# 23_-_SENSORS_CAN_IR.net
KiCad netlist of a schematic drawn in Altium Designer
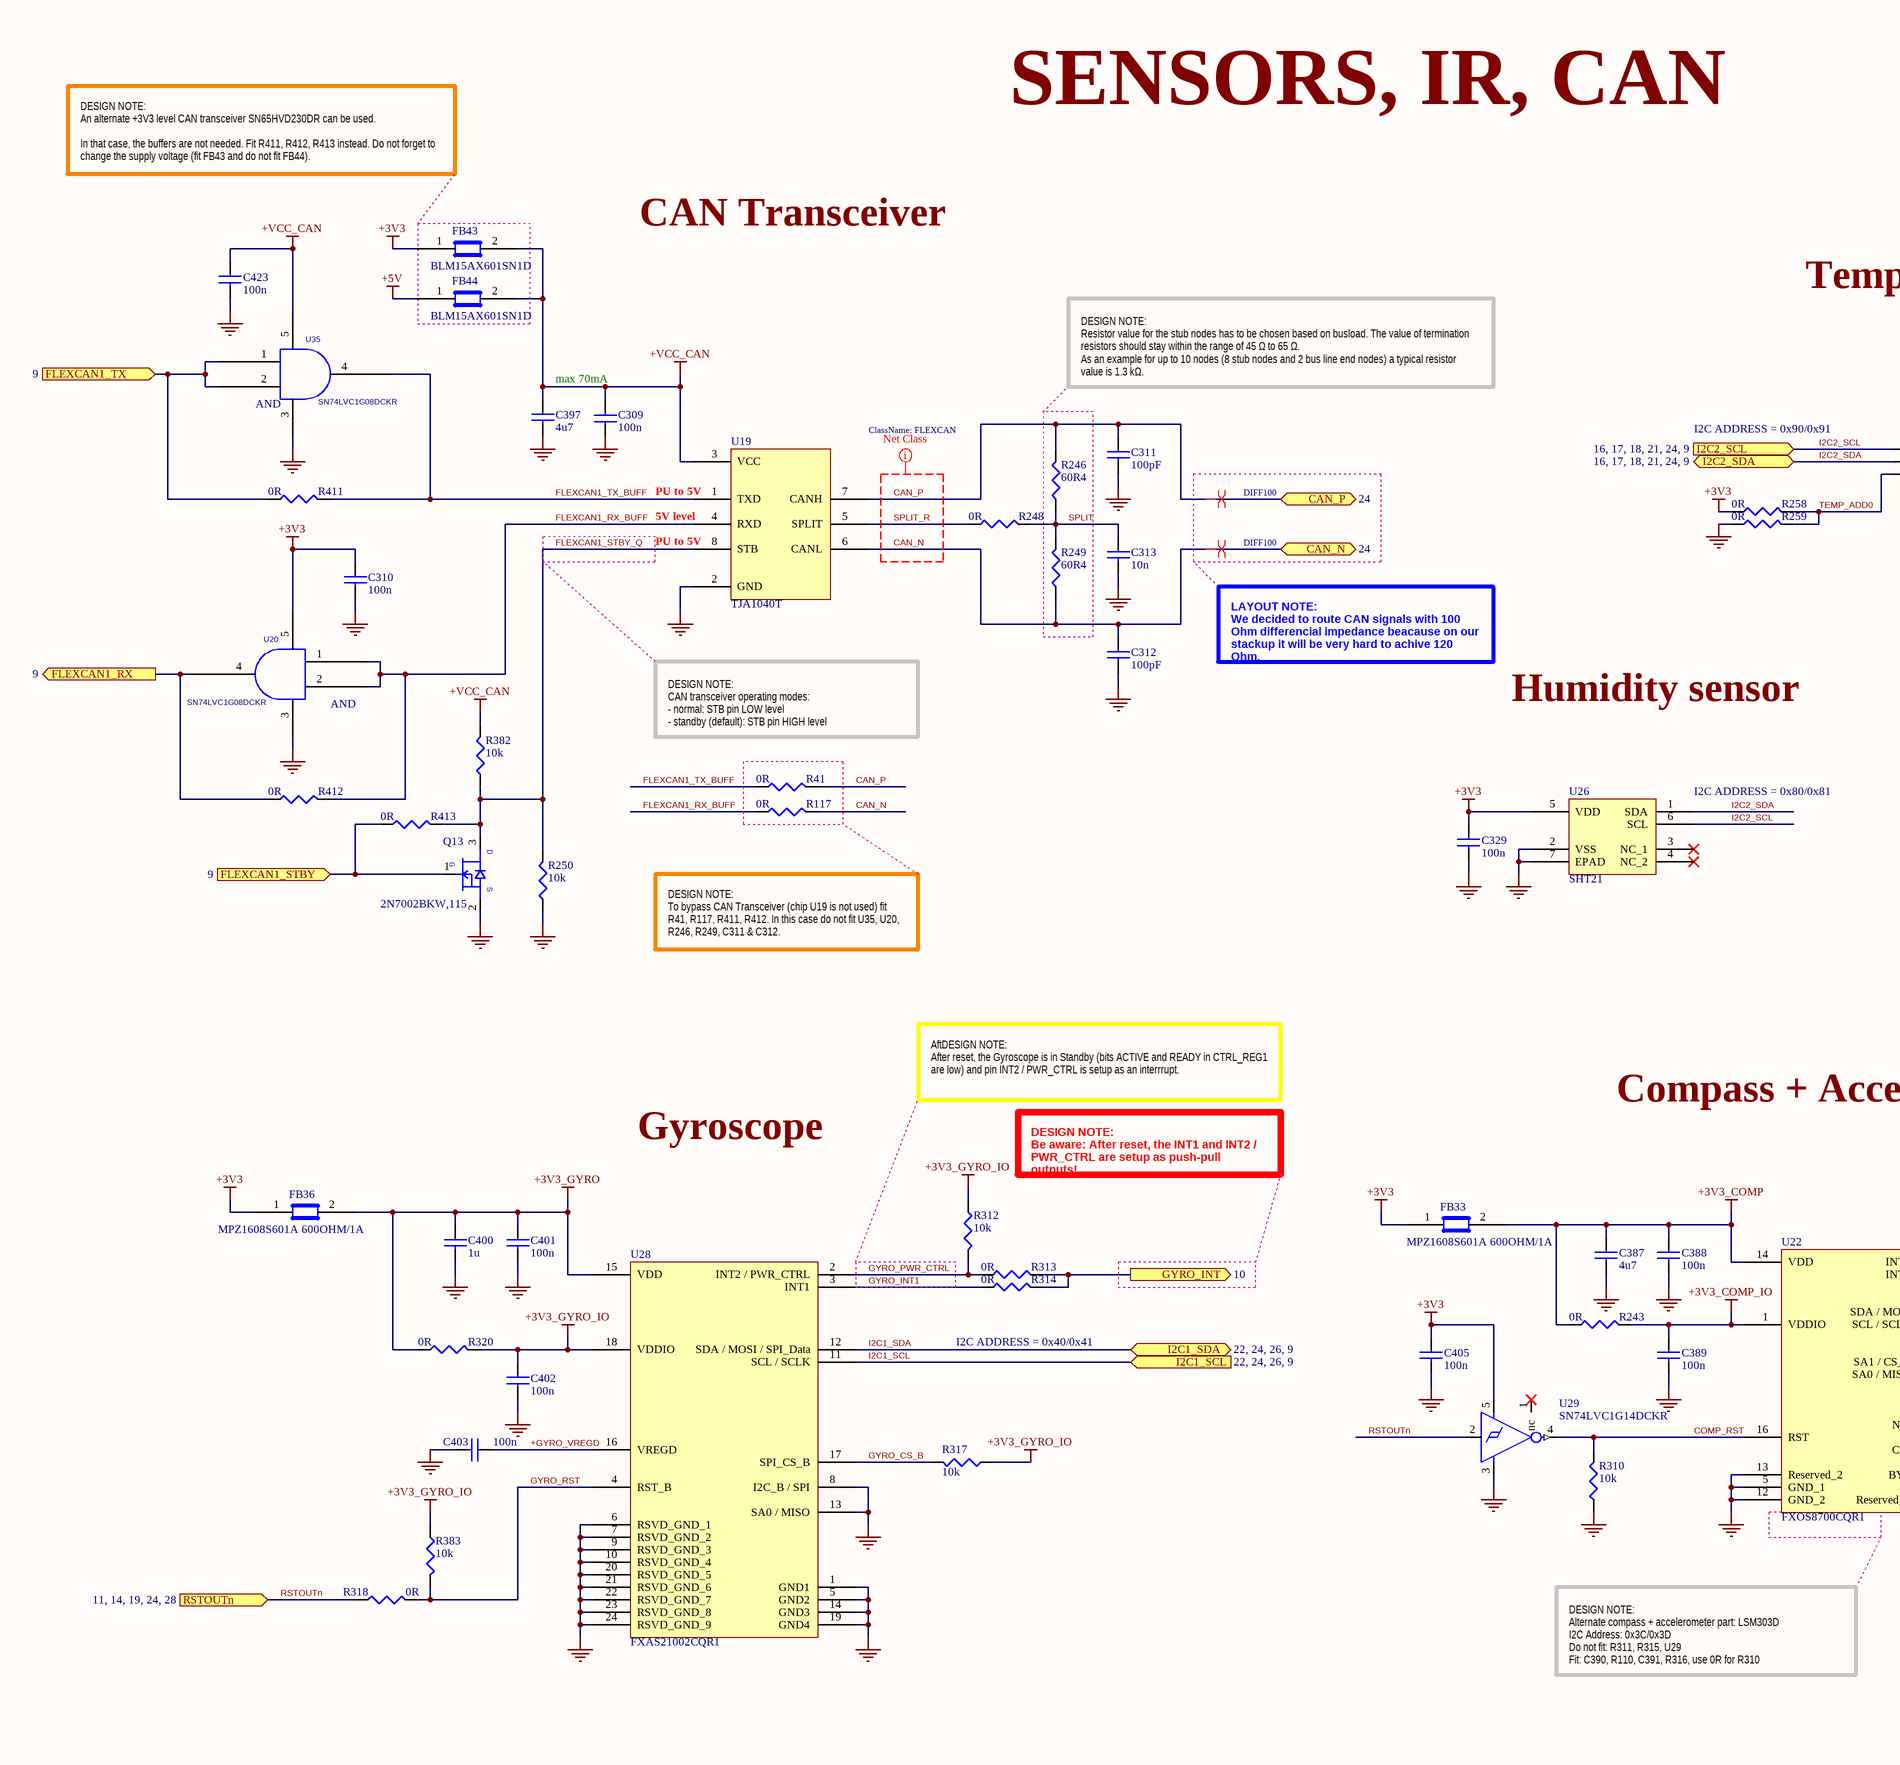
[diagram p0: [23] - SENSORS, CAN, IR.SchDoc, left]
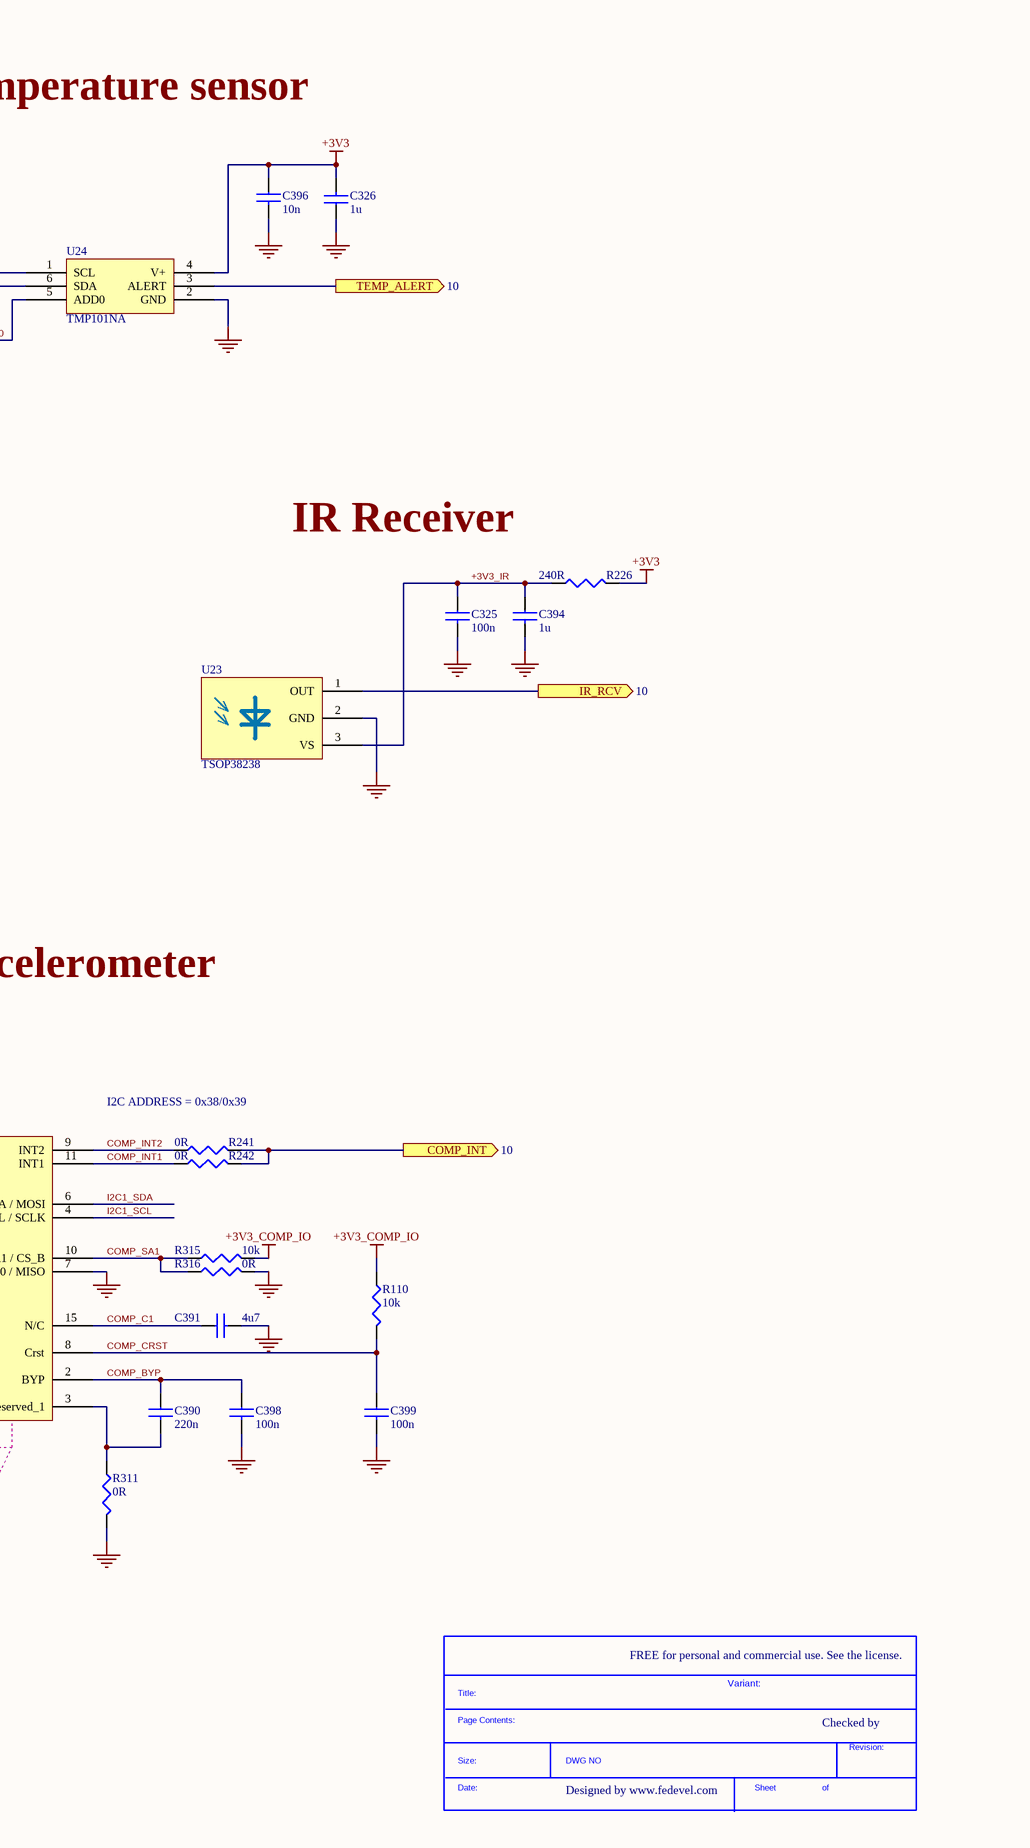
[diagram p1: [23] - SENSORS, CAN, IR.SchDoc, right]

(export (version "E")
  (design (tool "Eeschema 10.0.6"))
  (components
    (comp (ref "C309")
      (value "100n")
      (footprint "C0402")
      (description "CAP CER .10UF 50V X5R 10% 0402")
      (fields
        (field (name "MANUFACTURER") "TDK Corporation")
        (field (name "MANUFACTURER PART NUMBER") "C1005X5R1H104K")
      )
      (libsource (lib "Integrated_Library_FEDEVEL_APR_2015") (part "C1005X5R1H104K"))
    )
    (comp (ref "C310")
      (value "100n")
      (footprint "C0402")
      (description "CAP CER .10UF 50V X5R 10% 0402")
      (fields
        (field (name "MANUFACTURER") "TDK Corporation")
        (field (name "MANUFACTURER PART NUMBER") "C1005X5R1H104K")
      )
      (libsource (lib "Integrated_Library_FEDEVEL_APR_2015") (part "C1005X5R1H104K"))
    )
    (comp (ref "C311")
      (value "100pF")
      (footprint "C0402")
      (description "CAP CER 100PF 50V 5% NP0 0402")
      (fields
        (field (name "MANUFACTURER") "TDK Corporation")
        (field (name "MANUFACTURER PART NUMBER") "C1005C0G1H101J")
      )
      (libsource (lib "Integrated_Library_FEDEVEL_APR_2015") (part "C1005C0G1H101J"))
    )
    (comp (ref "C312")
      (value "100pF")
      (footprint "C0402")
      (description "CAP CER 100PF 50V 5% NP0 0402")
      (fields
        (field (name "MANUFACTURER") "TDK Corporation")
        (field (name "MANUFACTURER PART NUMBER") "C1005C0G1H101J")
      )
      (libsource (lib "Integrated_Library_FEDEVEL_APR_2015") (part "C1005C0G1H101J"))
    )
    (comp (ref "C313")
      (value "10n")
      (footprint "C0402")
      (description "CAP CER 10000PF 50V 10% X7R 0402")
      (fields
        (field (name "MANUFACTURER") "TDK Corporation")
        (field (name "MANUFACTURER PART NUMBER") "C1005X7R1H103K")
      )
      (libsource (lib "Integrated_Library_FEDEVEL_APR_2015") (part "C1005X7R1H103K"))
    )
    (comp (ref "C325")
      (value "100n")
      (footprint "C0402")
      (description "CAP CER .10UF 50V X5R 10% 0402")
      (fields
        (field (name "MANUFACTURER") "TDK Corporation")
        (field (name "MANUFACTURER PART NUMBER") "C1005X5R1H104K")
      )
      (libsource (lib "Integrated_Library_FEDEVEL_APR_2015") (part "C1005X5R1H104K"))
    )
    (comp (ref "C326")
      (value "1u")
      (footprint "C0402")
      (description "CAP CER 1.0UF 16V X5R 0402")
      (fields
        (field (name "MANUFACTURER") "TDK Corporation")
        (field (name "MANUFACTURER PART NUMBER") "C1005X5R1C105K")
      )
      (libsource (lib "Integrated_Library_FEDEVEL_APR_2015") (part "C1005X5R1C105K"))
    )
    (comp (ref "C329")
      (value "100n")
      (footprint "C0402")
      (description "CAP CER .10UF 50V X5R 10% 0402")
      (fields
        (field (name "MANUFACTURER") "TDK Corporation")
        (field (name "MANUFACTURER PART NUMBER") "C1005X5R1H104K")
      )
      (libsource (lib "Integrated_Library_FEDEVEL_APR_2015") (part "C1005X5R1H104K"))
    )
    (comp (ref "C387")
      (value "4u7")
      (footprint "C0402")
      (description "CAP CER 4.7UF 10V 20% X5R 0402")
      (fields
        (field (name "MANUFACTURER") "TDK Corporation")
        (field (name "MANUFACTURER PART NUMBER") "C1005X5R1A475M")
      )
      (libsource (lib "Integrated_Library_FEDEVEL_APR_2015") (part "C1005X5R1A475M"))
    )
    (comp (ref "C388")
      (value "100n")
      (footprint "C0402")
      (description "CAP CER .10UF 50V X5R 10% 0402")
      (fields
        (field (name "MANUFACTURER") "TDK Corporation")
        (field (name "MANUFACTURER PART NUMBER") "C1005X5R1H104K")
      )
      (libsource (lib "Integrated_Library_FEDEVEL_APR_2015") (part "C1005X5R1H104K"))
    )
    (comp (ref "C389")
      (value "100n")
      (footprint "C0402")
      (description "CAP CER .10UF 50V X5R 10% 0402")
      (fields
        (field (name "MANUFACTURER") "TDK Corporation")
        (field (name "MANUFACTURER PART NUMBER") "C1005X5R1H104K")
      )
      (libsource (lib "Integrated_Library_FEDEVEL_APR_2015") (part "C1005X5R1H104K"))
    )
    (comp (ref "C390")
      (value "220n")
      (footprint "C0402")
      (description "CAP CER .22UF 25V X5R 20% 0402")
      (fields
        (field (name "MANUFACTURER") "TDK Corporation")
        (field (name "MANUFACTURER PART NUMBER") "C1005X5R1E224M")
      )
      (libsource (lib "Integrated_Library_FEDEVEL_APR_2015") (part "C1005X5R1E224M"))
    )
    (comp (ref "C391")
      (value "4u7")
      (footprint "C0402")
      (description "CAP CER 4.7UF 10V 20% X5R 0402")
      (fields
        (field (name "MANUFACTURER") "TDK Corporation")
        (field (name "MANUFACTURER PART NUMBER") "C1005X5R1A475M")
      )
      (libsource (lib "Integrated_Library_FEDEVEL_APR_2015") (part "C1005X5R1A475M"))
    )
    (comp (ref "C394")
      (value "1u")
      (footprint "C0402")
      (description "CAP CER 1.0UF 16V X5R 0402")
      (fields
        (field (name "MANUFACTURER") "TDK Corporation")
        (field (name "MANUFACTURER PART NUMBER") "C1005X5R1C105K")
      )
      (libsource (lib "Integrated_Library_FEDEVEL_APR_2015") (part "C1005X5R1C105K"))
    )
    (comp (ref "C396")
      (value "10n")
      (footprint "C0402")
      (description "CAP CER 10000PF 50V 10% X7R 0402")
      (fields
        (field (name "MANUFACTURER") "TDK Corporation")
        (field (name "MANUFACTURER PART NUMBER") "C1005X7R1H103K")
      )
      (libsource (lib "Integrated_Library_FEDEVEL_APR_2015") (part "C1005X7R1H103K"))
    )
    (comp (ref "C397")
      (value "4u7")
      (footprint "C0402")
      (description "CAP CER 4.7UF 10V 20% X5R 0402")
      (fields
        (field (name "MANUFACTURER") "TDK Corporation")
        (field (name "MANUFACTURER PART NUMBER") "C1005X5R1A475M")
      )
      (libsource (lib "Integrated_Library_FEDEVEL_APR_2015") (part "C1005X5R1A475M"))
    )
    (comp (ref "C398")
      (value "100n")
      (footprint "C0402")
      (description "CAP CER .10UF 50V X5R 10% 0402")
      (fields
        (field (name "MANUFACTURER") "TDK Corporation")
        (field (name "MANUFACTURER PART NUMBER") "C1005X5R1H104K")
      )
      (libsource (lib "Integrated_Library_FEDEVEL_APR_2015") (part "C1005X5R1H104K"))
    )
    (comp (ref "C399")
      (value "100n")
      (footprint "C0402")
      (description "CAP CER .10UF 50V X5R 10% 0402")
      (fields
        (field (name "MANUFACTURER") "TDK Corporation")
        (field (name "MANUFACTURER PART NUMBER") "C1005X5R1H104K")
      )
      (libsource (lib "Integrated_Library_FEDEVEL_APR_2015") (part "C1005X5R1H104K"))
    )
    (comp (ref "C400")
      (value "1u")
      (footprint "C0402")
      (description "CAP CER 1.0UF 16V X5R 0402")
      (fields
        (field (name "MANUFACTURER") "TDK Corporation")
        (field (name "MANUFACTURER PART NUMBER") "C1005X5R1C105K")
      )
      (libsource (lib "Integrated_Library_FEDEVEL_APR_2015") (part "C1005X5R1C105K"))
    )
    (comp (ref "C401")
      (value "100n")
      (footprint "C0402")
      (description "CAP CER .10UF 50V X5R 10% 0402")
      (fields
        (field (name "MANUFACTURER") "TDK Corporation")
        (field (name "MANUFACTURER PART NUMBER") "C1005X5R1H104K")
      )
      (libsource (lib "Integrated_Library_FEDEVEL_APR_2015") (part "C1005X5R1H104K"))
    )
    (comp (ref "C402")
      (value "100n")
      (footprint "C0402")
      (description "CAP CER .10UF 50V X5R 10% 0402")
      (fields
        (field (name "MANUFACTURER") "TDK Corporation")
        (field (name "MANUFACTURER PART NUMBER") "C1005X5R1H104K")
      )
      (libsource (lib "Integrated_Library_FEDEVEL_APR_2015") (part "C1005X5R1H104K"))
    )
    (comp (ref "C403")
      (value "100n")
      (footprint "C0402")
      (description "CAP CER .10UF 50V X5R 10% 0402")
      (fields
        (field (name "MANUFACTURER") "TDK Corporation")
        (field (name "MANUFACTURER PART NUMBER") "C1005X5R1H104K")
      )
      (libsource (lib "Integrated_Library_FEDEVEL_APR_2015") (part "C1005X5R1H104K"))
    )
    (comp (ref "C405")
      (value "100n")
      (footprint "C0402")
      (description "CAP CER .10UF 50V X5R 10% 0402")
      (fields
        (field (name "MANUFACTURER") "TDK Corporation")
        (field (name "MANUFACTURER PART NUMBER") "C1005X5R1H104K")
      )
      (libsource (lib "Integrated_Library_FEDEVEL_APR_2015") (part "C1005X5R1H104K"))
    )
    (comp (ref "C423")
      (value "100n")
      (footprint "C0402")
      (description "CAP CER .10UF 50V X5R 10% 0402")
      (fields
        (field (name "MANUFACTURER") "TDK Corporation")
        (field (name "MANUFACTURER PART NUMBER") "C1005X5R1H104K")
      )
      (libsource (lib "Integrated_Library_FEDEVEL_APR_2015") (part "C1005X5R1H104K"))
    )
    (comp (ref "FB33")
      (value "MPZ1608S601A 600OHM/1A")
      (footprint "C0603")
      (description "FERRITE CHIP BEAD 600 OHM SMD 1A")
      (fields
        (field (name "MANUFACTURER") "TDK Corporation")
        (field (name "MANUFACTURER PART NUMBER") "MPZ1608S601A")
      )
      (libsource (lib "Integrated_Library_FEDEVEL_APR_2015") (part "MPZ1608S601A"))
    )
    (comp (ref "FB36")
      (value "MPZ1608S601A 600OHM/1A")
      (footprint "C0603")
      (description "FERRITE CHIP BEAD 600 OHM SMD 1A")
      (fields
        (field (name "MANUFACTURER") "TDK Corporation")
        (field (name "MANUFACTURER PART NUMBER") "MPZ1608S601A")
      )
      (libsource (lib "Integrated_Library_FEDEVEL_APR_2015") (part "MPZ1608S601A"))
    )
    (comp (ref "FB43")
      (value "BLM15AX601SN1D")
      (footprint "C0402")
      (description "FERRITE CHIP 600 OHM 0402 420mA")
      (fields (field (name "MANUFACTURER") "Murata Electronics North America"))
      (libsource (lib "Integrated_Library_FEDEVEL_APR_2015") (part "BLM15AX601SN1D"))
    )
    (comp (ref "FB44")
      (value "BLM15AX601SN1D")
      (footprint "C0402")
      (description "FERRITE CHIP 600 OHM 0402 420mA")
      (fields (field (name "MANUFACTURER") "Murata Electronics North America"))
      (libsource (lib "Integrated_Library_FEDEVEL_APR_2015") (part "BLM15AX601SN1D"))
    )
    (comp (ref "Q13")
      (value "2N7002BKW,115")
      (footprint "SC70_SOT323")
      (description "MOSFET N-CH 60V 310MA SOT323")
      (fields (field (name "MANUFACTURER") "NXP Semiconductors"))
      (libsource (lib "Integrated_Library_FEDEVEL_APR_2015") (part "2N7002BKW,115"))
    )
    (comp (ref "R41")
      (value "0R")
      (footprint "R0402")
      (description "RES 0.0 OHM 1/16W 0402 SMD")
      (fields
        (field (name "MANUFACTURER") "Yageo")
        (field (name "MANUFACTURER PART NUMBER") "RC0402JR-070RL")
      )
      (libsource (lib "Integrated_Library_FEDEVEL_APR_2015") (part "RC0402JR-070RL"))
    )
    (comp (ref "R110")
      (value "10k")
      (footprint "R0402")
      (description "RES 10.0K OHM 1/16W 1% 0402 SMD")
      (fields
        (field (name "MANUFACTURER") "Yageo")
        (field (name "MANUFACTURER PART NUMBER") "RC0402FR-0710KL")
      )
      (libsource (lib "Integrated_Library_FEDEVEL_APR_2015") (part "RC0402FR-0710KL"))
    )
    (comp (ref "R117")
      (value "0R")
      (footprint "R0402")
      (description "RES 0.0 OHM 1/16W 0402 SMD")
      (fields
        (field (name "MANUFACTURER") "Yageo")
        (field (name "MANUFACTURER PART NUMBER") "RC0402JR-070RL")
      )
      (libsource (lib "Integrated_Library_FEDEVEL_APR_2015") (part "RC0402JR-070RL"))
    )
    (comp (ref "R226")
      (value "240R")
      (footprint "R0402")
      (description "RES TF 240 OHM 1% 0.0625W 0402")
      (fields
        (field (name "MANUFACTURER") "Stackpole Electronics Inc")
        (field (name "MANUFACTURER PART NUMBER") "RMCF0402FT240R")
      )
      (libsource (lib "Integrated_Library_FEDEVEL_APR_2015") (part "RMCF0402FT240R"))
    )
    (comp (ref "R241")
      (value "0R")
      (footprint "R0402")
      (description "RES 0.0 OHM 1/16W 0402 SMD")
      (fields
        (field (name "MANUFACTURER") "Yageo")
        (field (name "MANUFACTURER PART NUMBER") "RC0402JR-070RL")
      )
      (libsource (lib "Integrated_Library_FEDEVEL_APR_2015") (part "RC0402JR-070RL"))
    )
    (comp (ref "R242")
      (value "0R")
      (footprint "R0402")
      (description "RES 0.0 OHM 1/16W 0402 SMD")
      (fields
        (field (name "MANUFACTURER") "Yageo")
        (field (name "MANUFACTURER PART NUMBER") "RC0402JR-070RL")
      )
      (libsource (lib "Integrated_Library_FEDEVEL_APR_2015") (part "RC0402JR-070RL"))
    )
    (comp (ref "R243")
      (value "0R")
      (footprint "R0402")
      (description "RES 0.0 OHM 1/16W 0402 SMD")
      (fields
        (field (name "MANUFACTURER") "Yageo")
        (field (name "MANUFACTURER PART NUMBER") "RC0402JR-070RL")
      )
      (libsource (lib "Integrated_Library_FEDEVEL_APR_2015") (part "RC0402JR-070RL"))
    )
    (comp (ref "R246")
      (value "60R4")
      (footprint "R0402")
      (description "RES SMD 60.4 OHM 1% 1/16W 0402")
      (fields
        (field (name "MANUFACTURER") "Yageo")
        (field (name "MANUFACTURER PART NUMBER") "RC0402FR-0760R4L")
        (field (name ".CREATOR") "MM")
        (field (name ".CHECKED PCB") "MM")
        (field (name ".CHECKED SCH") "MM")
      )
      (libsource (lib "Integrated_Library_FEDEVEL_APR_2015") (part "RC0402FR-0760R4L"))
    )
    (comp (ref "R248")
      (value "0R")
      (footprint "R0402")
      (description "RES 0.0 OHM 1/16W 0402 SMD")
      (fields
        (field (name "MANUFACTURER") "Yageo")
        (field (name "MANUFACTURER PART NUMBER") "RC0402JR-070RL")
      )
      (libsource (lib "Integrated_Library_FEDEVEL_APR_2015") (part "RC0402JR-070RL"))
    )
    (comp (ref "R249")
      (value "60R4")
      (footprint "R0402")
      (description "RES SMD 60.4 OHM 1% 1/16W 0402")
      (fields
        (field (name "MANUFACTURER") "Yageo")
        (field (name "MANUFACTURER PART NUMBER") "RC0402FR-0760R4L")
        (field (name ".CREATOR") "MM")
        (field (name ".CHECKED PCB") "MM")
        (field (name ".CHECKED SCH") "MM")
      )
      (libsource (lib "Integrated_Library_FEDEVEL_APR_2015") (part "RC0402FR-0760R4L"))
    )
    (comp (ref "R250")
      (value "10k")
      (footprint "R0402")
      (description "RES 10.0K OHM 1/16W 1% 0402 SMD")
      (fields
        (field (name "MANUFACTURER") "Yageo")
        (field (name "MANUFACTURER PART NUMBER") "RC0402FR-0710KL")
      )
      (libsource (lib "Integrated_Library_FEDEVEL_APR_2015") (part "RC0402FR-0710KL"))
    )
    (comp (ref "R258")
      (value "0R")
      (footprint "R0402")
      (description "RES 0.0 OHM 1/16W 0402 SMD")
      (fields
        (field (name "MANUFACTURER") "Yageo")
        (field (name "MANUFACTURER PART NUMBER") "RC0402JR-070RL")
      )
      (libsource (lib "Integrated_Library_FEDEVEL_APR_2015") (part "RC0402JR-070RL"))
    )
    (comp (ref "R259")
      (value "0R")
      (footprint "R0402")
      (description "RES 0.0 OHM 1/16W 0402 SMD")
      (fields
        (field (name "MANUFACTURER") "Yageo")
        (field (name "MANUFACTURER PART NUMBER") "RC0402JR-070RL")
      )
      (libsource (lib "Integrated_Library_FEDEVEL_APR_2015") (part "RC0402JR-070RL"))
    )
    (comp (ref "R310")
      (value "10k")
      (footprint "R0402")
      (description "RES 10.0K OHM 1/16W 1% 0402 SMD")
      (fields
        (field (name "MANUFACTURER") "Yageo")
        (field (name "MANUFACTURER PART NUMBER") "RC0402FR-0710KL")
      )
      (libsource (lib "Integrated_Library_FEDEVEL_APR_2015") (part "RC0402FR-0710KL"))
    )
    (comp (ref "R311")
      (value "0R")
      (footprint "R0402")
      (description "RES 0.0 OHM 1/16W 0402 SMD")
      (fields
        (field (name "MANUFACTURER") "Yageo")
        (field (name "MANUFACTURER PART NUMBER") "RC0402JR-070RL")
      )
      (libsource (lib "Integrated_Library_FEDEVEL_APR_2015") (part "RC0402JR-070RL"))
    )
    (comp (ref "R312")
      (value "10k")
      (footprint "R0402")
      (description "RES 10.0K OHM 1/16W 1% 0402 SMD")
      (fields
        (field (name "MANUFACTURER") "Yageo")
        (field (name "MANUFACTURER PART NUMBER") "RC0402FR-0710KL")
      )
      (libsource (lib "Integrated_Library_FEDEVEL_APR_2015") (part "RC0402FR-0710KL"))
    )
    (comp (ref "R313")
      (value "0R")
      (footprint "R0402")
      (description "RES 0.0 OHM 1/16W 0402 SMD")
      (fields
        (field (name "MANUFACTURER") "Yageo")
        (field (name "MANUFACTURER PART NUMBER") "RC0402JR-070RL")
      )
      (libsource (lib "Integrated_Library_FEDEVEL_APR_2015") (part "RC0402JR-070RL"))
    )
    (comp (ref "R314")
      (value "0R")
      (footprint "R0402")
      (description "RES 0.0 OHM 1/16W 0402 SMD")
      (fields
        (field (name "MANUFACTURER") "Yageo")
        (field (name "MANUFACTURER PART NUMBER") "RC0402JR-070RL")
      )
      (libsource (lib "Integrated_Library_FEDEVEL_APR_2015") (part "RC0402JR-070RL"))
    )
    (comp (ref "R315")
      (value "10k")
      (footprint "R0402")
      (description "RES 10.0K OHM 1/16W 1% 0402 SMD")
      (fields
        (field (name "MANUFACTURER") "Yageo")
        (field (name "MANUFACTURER PART NUMBER") "RC0402FR-0710KL")
      )
      (libsource (lib "Integrated_Library_FEDEVEL_APR_2015") (part "RC0402FR-0710KL"))
    )
    (comp (ref "R316")
      (value "0R")
      (footprint "R0402")
      (description "RES 0.0 OHM 1/16W 0402 SMD")
      (fields
        (field (name "MANUFACTURER") "Yageo")
        (field (name "MANUFACTURER PART NUMBER") "RC0402JR-070RL")
      )
      (libsource (lib "Integrated_Library_FEDEVEL_APR_2015") (part "RC0402JR-070RL"))
    )
    (comp (ref "R317")
      (value "10k")
      (footprint "R0402")
      (description "RES 10.0K OHM 1/16W 1% 0402 SMD")
      (fields
        (field (name "MANUFACTURER") "Yageo")
        (field (name "MANUFACTURER PART NUMBER") "RC0402FR-0710KL")
      )
      (libsource (lib "Integrated_Library_FEDEVEL_APR_2015") (part "RC0402FR-0710KL"))
    )
    (comp (ref "R318")
      (value "0R")
      (footprint "R0402")
      (description "RES 0.0 OHM 1/16W 0402 SMD")
      (fields
        (field (name "MANUFACTURER") "Yageo")
        (field (name "MANUFACTURER PART NUMBER") "RC0402JR-070RL")
      )
      (libsource (lib "Integrated_Library_FEDEVEL_APR_2015") (part "RC0402JR-070RL"))
    )
    (comp (ref "R320")
      (value "0R")
      (footprint "R0402")
      (description "RES 0.0 OHM 1/16W 0402 SMD")
      (fields
        (field (name "MANUFACTURER") "Yageo")
        (field (name "MANUFACTURER PART NUMBER") "RC0402JR-070RL")
      )
      (libsource (lib "Integrated_Library_FEDEVEL_APR_2015") (part "RC0402JR-070RL"))
    )
    (comp (ref "R382")
      (value "10k")
      (footprint "R0402")
      (description "RES 10.0K OHM 1/16W 1% 0402 SMD")
      (fields
        (field (name "MANUFACTURER") "Yageo")
        (field (name "MANUFACTURER PART NUMBER") "RC0402FR-0710KL")
      )
      (libsource (lib "Integrated_Library_FEDEVEL_APR_2015") (part "RC0402FR-0710KL"))
    )
    (comp (ref "R383")
      (value "10k")
      (footprint "R0402")
      (description "RES 10.0K OHM 1/16W 1% 0402 SMD")
      (fields
        (field (name "MANUFACTURER") "Yageo")
        (field (name "MANUFACTURER PART NUMBER") "RC0402FR-0710KL")
      )
      (libsource (lib "Integrated_Library_FEDEVEL_APR_2015") (part "RC0402FR-0710KL"))
    )
    (comp (ref "R411")
      (value "0R")
      (footprint "R0402")
      (description "RES 0.0 OHM 1/16W 0402 SMD")
      (fields
        (field (name "MANUFACTURER") "Yageo")
        (field (name "MANUFACTURER PART NUMBER") "RC0402JR-070RL")
      )
      (libsource (lib "Integrated_Library_FEDEVEL_APR_2015") (part "RC0402JR-070RL"))
    )
    (comp (ref "R412")
      (value "0R")
      (footprint "R0402")
      (description "RES 0.0 OHM 1/16W 0402 SMD")
      (fields
        (field (name "MANUFACTURER") "Yageo")
        (field (name "MANUFACTURER PART NUMBER") "RC0402JR-070RL")
      )
      (libsource (lib "Integrated_Library_FEDEVEL_APR_2015") (part "RC0402JR-070RL"))
    )
    (comp (ref "R413")
      (value "0R")
      (footprint "R0402")
      (description "RES 0.0 OHM 1/16W 0402 SMD")
      (fields
        (field (name "MANUFACTURER") "Yageo")
        (field (name "MANUFACTURER PART NUMBER") "RC0402JR-070RL")
      )
      (libsource (lib "Integrated_Library_FEDEVEL_APR_2015") (part "RC0402JR-070RL"))
    )
    (comp (ref "U19")
      (value "TJA1040T")
      (footprint "8_SOIC_3.9MM")
      (description "IC TRANSCEIVER CAN 8SOIC")
      (fields
        (field (name "MANUFACTURER") "NXP Semiconductors")
        (field (name "MANUFACTURER PART NUMBER") "TJA1040T/CM,118")
        (field (name ".CREATOR") "MM")
        (field (name ".CHECKED PCB") "MM")
        (field (name ".CHECKED SCH") "MM")
      )
      (libsource (lib "Integrated_Library_FEDEVEL_APR_2015") (part "TJA1040T/CM,118"))
    )
    (comp (ref "U20")
      (value "SN74LVC1G08DCKR")
      (footprint "SC70_5")
      (description "SINGLE POSITIVE AND GATE SC-70")
      (fields (field (name "MANUFACTURER") "Texas Instruments"))
      (libsource (lib "") (part "SN74LVC1G08DCKR_1"))
    )
    (comp (ref "U22")
      (value "FXOS8700CQR1")
      (footprint "QFN16_3x3mm")
      (description "SENSOR XTRINSIC 6-AXIS QFN")
      (fields
        (field (name "MANUFACTURER") "Freescale Semiconductor")
        (field (name ".CHECKED PCB") "MM")
        (field (name ".CHECKED SCH") "MM")
        (field (name ".CREATOR") "MM")
      )
      (libsource (lib "Integrated_Library_FEDEVEL_APR_2015") (part "FXOS8700CQR1"))
    )
    (comp (ref "U23")
      (value "TSOP38238")
      (footprint "TSOP382")
      (description "IC IR RCVR MOD 38KHZ DOME AXIAL")
      (fields
        (field (name "MANUFACTURER") "Vishay Semiconductor Opto Division")
        (field (name ".CREATOR") "MM")
        (field (name ".CHECKED PCB") "MM")
        (field (name ".CHECKED SCH") "MM")
      )
      (libsource (lib "Integrated_Library_FEDEVEL_APR_2015") (part "TSOP38238"))
    )
    (comp (ref "U24")
      (value "TMP101NA")
      (footprint "SOT23-6_DBV6")
      (description "IC DIGITAL TEMP SENSOR SOT23-6")
      (fields
        (field (name "MANUFACTURER") "Texas Instruments")
        (field (name "MANUFACTURER PART NUMBER") "TMP101NA/3K")
        (field (name ".CHECKED PCB") "RF(LibOnly), MM")
        (field (name ".CHECKED SCH") "RF")
      )
      (libsource (lib "Integrated_Library_FEDEVEL_APR_2015") (part "TMP101NA"))
    )
    (comp (ref "U26")
      (value "SHT21")
      (footprint "6_DFN_3mmx3mm")
      (description "SENSIRION - SHT21 - SENSOR, HUMIDITY & TEMP, 3X3MM, 2%")
      (fields
        (field (name "MANUFACTURER") "SENSIRION")
        (field (name ".CREATOR") "MM")
        (field (name ".CHECKED PCB") "MM")
        (field (name ".CHECKED SCH") "MM")
      )
      (libsource (lib "Integrated_Library_FEDEVEL_APR_2015") (part "SHT21"))
    )
    (comp (ref "U28")
      (value "FXAS21002CQR1")
      (footprint "QFN24_4x4MM")
      (description "GYROSCOPE 3-AXIS 24QFN")
      (fields
        (field (name "MANUFACTURER") "Freescale Semiconductor")
        (field (name ".CHECKED PCB") "MM")
        (field (name ".CHECKED SCH") "MM")
        (field (name ".CREATOR") "MM")
      )
      (libsource (lib "Integrated_Library_FEDEVEL_APR_2015") (part "FXAS21002CQR1"))
    )
    (comp (ref "U29")
      (value "SN74LVC1G14DCKR")
      (footprint "SC70_5")
      (description "IC SGL SCHMT-TRIG INVERT SC70-5")
      (fields
        (field (name "MANUFACTURER") "Texas Instruments")
        (field (name ".CHECKED PCB") "MM, paper model not checked")
        (field (name ".CHECKED SCH") "MM")
        (field (name ".CREATOR") "MM")
      )
      (libsource (lib "Integrated_Library_FEDEVEL_APR_2015") (part "SN74LVC1G14DCKR"))
    )
    (comp (ref "U35")
      (value "SN74LVC1G08DCKR")
      (footprint "SC70_5")
      (description "SINGLE POSITIVE AND GATE SC-70")
      (fields (field (name "MANUFACTURER") "Texas Instruments"))
      (libsource (lib "Integrated_Library_FEDEVEL_APR_2015") (part "SN74LVC1G08DCKR"))
    )
  )
  (nets
    (net (code "1") (name "+3V3") (class "Default")
      (node (ref "C310") (pin "1") (pinfunction "1_1") (pintype "passive"))
      (node (ref "C326") (pin "2") (pinfunction "2_2") (pintype "passive"))
      (node (ref "C329") (pin "1") (pinfunction "1_1") (pintype "passive"))
      (node (ref "C396") (pin "1") (pinfunction "1_1") (pintype "passive"))
      (node (ref "C405") (pin "1") (pinfunction "1_1") (pintype "passive"))
      (node (ref "FB33") (pin "1") (pinfunction "1_1") (pintype "passive"))
      (node (ref "FB36") (pin "1") (pinfunction "1_1") (pintype "passive"))
      (node (ref "FB43") (pin "1") (pinfunction "1_1") (pintype "passive"))
      (node (ref "R226") (pin "2") (pinfunction "2_2") (pintype "passive"))
      (node (ref "R258") (pin "1") (pinfunction "1_1") (pintype "passive"))
      (node (ref "U20") (pin "5") (pinfunction "VCC_5") (pintype "power_in"))
      (node (ref "U24") (pin "4") (pinfunction "V+_4") (pintype "passive"))
      (node (ref "U26") (pin "5") (pinfunction "VDD_5") (pintype "passive"))
      (node (ref "U29") (pin "5") (pinfunction "NC1_5") (pintype "passive"))
    )
    (net (code "2") (name "+3V3_COMP") (class "Default")
      (node (ref "C387") (pin "1") (pinfunction "1_1") (pintype "passive"))
      (node (ref "C388") (pin "1") (pinfunction "1_1") (pintype "passive"))
      (node (ref "FB33") (pin "2") (pinfunction "2_2") (pintype "passive"))
      (node (ref "R243") (pin "1") (pinfunction "1_1") (pintype "passive"))
      (node (ref "U22") (pin "14") (pinfunction "VDD_14") (pintype "passive"))
    )
    (net (code "3") (name "+3V3_COMP_IO") (class "Default")
      (node (ref "C389") (pin "1") (pinfunction "1_1") (pintype "passive"))
      (node (ref "R110") (pin "1") (pinfunction "1_1") (pintype "passive"))
      (node (ref "R243") (pin "2") (pinfunction "2_2") (pintype "passive"))
      (node (ref "R315") (pin "2") (pinfunction "2_2") (pintype "passive"))
      (node (ref "U22") (pin "1") (pinfunction "VDDIO_1") (pintype "passive"))
    )
    (net (code "4") (name "+3V3_GYRO") (class "Default")
      (node (ref "C400") (pin "1") (pinfunction "1_1") (pintype "passive"))
      (node (ref "C401") (pin "1") (pinfunction "1_1") (pintype "passive"))
      (node (ref "FB36") (pin "2") (pinfunction "2_2") (pintype "passive"))
      (node (ref "R320") (pin "1") (pinfunction "1_1") (pintype "passive"))
      (node (ref "U28") (pin "15") (pinfunction "VDD_15") (pintype "passive"))
    )
    (net (code "5") (name "+3V3_GYRO_IO") (class "Default")
      (node (ref "C402") (pin "1") (pinfunction "1_1") (pintype "passive"))
      (node (ref "R312") (pin "1") (pinfunction "1_1") (pintype "passive"))
      (node (ref "R317") (pin "1") (pinfunction "1_1") (pintype "passive"))
      (node (ref "R320") (pin "2") (pinfunction "2_2") (pintype "passive"))
      (node (ref "R383") (pin "1") (pinfunction "1_1") (pintype "passive"))
      (node (ref "U28") (pin "18") (pinfunction "VDDIO_18") (pintype "passive"))
    )
    (net (code "6") (name "+5V") (class "Default")
      (node (ref "FB44") (pin "1") (pinfunction "1_1") (pintype "passive"))
    )
    (net (code "7") (name "+VCC_CAN") (class "Default")
      (node (ref "C309") (pin "2") (pinfunction "2_2") (pintype "passive"))
      (node (ref "C397") (pin "1") (pinfunction "1_1") (pintype "passive"))
      (node (ref "C423") (pin "1") (pinfunction "1_1") (pintype "passive"))
      (node (ref "FB43") (pin "2") (pinfunction "2_2") (pintype "passive"))
      (node (ref "FB44") (pin "2") (pinfunction "2_2") (pintype "passive"))
      (node (ref "R382") (pin "2") (pinfunction "2_2") (pintype "passive"))
      (node (ref "U19") (pin "3") (pinfunction "VCC_3") (pintype "passive"))
      (node (ref "U35") (pin "5") (pinfunction "VCC_5") (pintype "power_in"))
    )
    (net (code "8") (name "/+3V3_IR") (class "Default")
      (node (ref "C325") (pin "1") (pinfunction "1_1") (pintype "passive"))
      (node (ref "C394") (pin "1") (pinfunction "1_1") (pintype "passive"))
      (node (ref "R226") (pin "1") (pinfunction "1_1") (pintype "passive"))
      (node (ref "U23") (pin "3") (pinfunction "VS_3") (pintype "passive"))
    )
    (net (code "9") (name "/+GYRO_VREGD") (class "Default")
      (node (ref "C403") (pin "1") (pinfunction "1_1") (pintype "passive"))
      (node (ref "U28") (pin "16") (pinfunction "VREGD_16") (pintype "passive"))
    )
    (net (code "10") (name "/CAN_N") (class "Default")
      (node (ref "C312") (pin "1") (pinfunction "1_1") (pintype "passive"))
      (node (ref "R117") (pin "2") (pinfunction "2_2") (pintype "passive"))
      (node (ref "R249") (pin "1") (pinfunction "1_1") (pintype "passive"))
      (node (ref "U19") (pin "6") (pinfunction "CANL_6") (pintype "passive"))
    )
    (net (code "11") (name "/CAN_P") (class "Default")
      (node (ref "C311") (pin "1") (pinfunction "1_1") (pintype "passive"))
      (node (ref "R246") (pin "2") (pinfunction "2_2") (pintype "passive"))
      (node (ref "R41") (pin "2") (pinfunction "2_2") (pintype "passive"))
      (node (ref "U19") (pin "7") (pinfunction "CANH_7") (pintype "passive"))
    )
    (net (code "12") (name "/COMP_BYP") (class "Default")
      (node (ref "C390") (pin "1") (pinfunction "1_1") (pintype "passive"))
      (node (ref "C398") (pin "1") (pinfunction "1_1") (pintype "passive"))
      (node (ref "U22") (pin "2") (pinfunction "BYP_2") (pintype "passive"))
    )
    (net (code "13") (name "/COMP_C1") (class "Default")
      (node (ref "C391") (pin "1") (pinfunction "1_1") (pintype "passive"))
      (node (ref "U22") (pin "15") (pinfunction "N/C_15") (pintype "passive"))
    )
    (net (code "14") (name "/COMP_CRST") (class "Default")
      (node (ref "C399") (pin "1") (pinfunction "1_1") (pintype "passive"))
      (node (ref "R110") (pin "2") (pinfunction "2_2") (pintype "passive"))
      (node (ref "U22") (pin "8") (pinfunction "Crst_8") (pintype "passive"))
    )
    (net (code "15") (name "/COMP_INT") (class "Default")
      (node (ref "R241") (pin "2") (pinfunction "2_2") (pintype "passive"))
      (node (ref "R242") (pin "2") (pinfunction "2_2") (pintype "passive"))
    )
    (net (code "16") (name "/COMP_INT1") (class "Default")
      (node (ref "R242") (pin "1") (pinfunction "1_1") (pintype "passive"))
      (node (ref "U22") (pin "11") (pinfunction "INT1_11") (pintype "passive"))
    )
    (net (code "17") (name "/COMP_INT2") (class "Default")
      (node (ref "R241") (pin "1") (pinfunction "1_1") (pintype "passive"))
      (node (ref "U22") (pin "9") (pinfunction "INT2_9") (pintype "passive"))
    )
    (net (code "18") (name "/COMP_RST") (class "Default")
      (node (ref "R310") (pin "2") (pinfunction "2_2") (pintype "passive"))
      (node (ref "U22") (pin "16") (pinfunction "RST_16") (pintype "passive"))
      (node (ref "U29") (pin "4") (pinfunction "O_4") (pintype "output"))
    )
    (net (code "19") (name "/COMP_SA1") (class "Default")
      (node (ref "R315") (pin "1") (pinfunction "1_1") (pintype "passive"))
      (node (ref "R316") (pin "1") (pinfunction "1_1") (pintype "passive"))
      (node (ref "U22") (pin "10") (pinfunction "SA1_/_CS_B_10") (pintype "passive"))
    )
    (net (code "20") (name "/FLEXCAN1_RX") (class "Default")
      (node (ref "R412") (pin "1") (pinfunction "1_1") (pintype "passive"))
      (node (ref "U20") (pin "4") (pinfunction "Y_4") (pintype "passive"))
    )
    (net (code "21") (name "/FLEXCAN1_RX_BUFF") (class "Default")
      (node (ref "R117") (pin "1") (pinfunction "1_1") (pintype "passive"))
      (node (ref "R412") (pin "2") (pinfunction "2_2") (pintype "passive"))
      (node (ref "U19") (pin "4") (pinfunction "RXD_4") (pintype "passive"))
      (node (ref "U20") (pin "1") (pinfunction "A_1") (pintype "passive"))
      (node (ref "U20") (pin "2") (pinfunction "B_2") (pintype "passive"))
    )
    (net (code "22") (name "/FLEXCAN1_STBY") (class "Default")
      (node (ref "Q13") (pin "1") (pinfunction "GATE_1") (pintype "passive"))
      (node (ref "R413") (pin "1") (pinfunction "1_1") (pintype "passive"))
    )
    (net (code "23") (name "/FLEXCAN1_STBY_Q") (class "Default")
      (node (ref "Q13") (pin "3") (pinfunction "DRAIN_3") (pintype "passive"))
      (node (ref "R250") (pin "2") (pinfunction "2_2") (pintype "passive"))
      (node (ref "R382") (pin "1") (pinfunction "1_1") (pintype "passive"))
      (node (ref "R413") (pin "2") (pinfunction "2_2") (pintype "passive"))
      (node (ref "U19") (pin "8") (pinfunction "STB_8") (pintype "passive"))
    )
    (net (code "24") (name "/FLEXCAN1_TX") (class "Default")
      (node (ref "R411") (pin "1") (pinfunction "1_1") (pintype "passive"))
      (node (ref "U35") (pin "1") (pinfunction "A_1") (pintype "passive"))
      (node (ref "U35") (pin "2") (pinfunction "B_2") (pintype "passive"))
    )
    (net (code "25") (name "/FLEXCAN1_TX_BUFF") (class "Default")
      (node (ref "R41") (pin "1") (pinfunction "1_1") (pintype "passive"))
      (node (ref "R411") (pin "2") (pinfunction "2_2") (pintype "passive"))
      (node (ref "U19") (pin "1") (pinfunction "TXD_1") (pintype "passive"))
      (node (ref "U35") (pin "4") (pinfunction "Y_4") (pintype "passive"))
    )
    (net (code "26") (name "/GYRO_CS_B") (class "Default")
      (node (ref "R317") (pin "2") (pinfunction "2_2") (pintype "passive"))
      (node (ref "U28") (pin "17") (pinfunction "SPI_CS_B_17") (pintype "passive"))
    )
    (net (code "27") (name "/GYRO_INT") (class "Default")
      (node (ref "R313") (pin "2") (pinfunction "2_2") (pintype "passive"))
      (node (ref "R314") (pin "2") (pinfunction "2_2") (pintype "passive"))
    )
    (net (code "28") (name "/GYRO_INT1") (class "Default")
      (node (ref "R314") (pin "1") (pinfunction "1_1") (pintype "passive"))
      (node (ref "U28") (pin "3") (pinfunction "INT1_3") (pintype "passive"))
    )
    (net (code "29") (name "/GYRO_PWR_CTRL") (class "Default")
      (node (ref "R312") (pin "2") (pinfunction "2_2") (pintype "passive"))
      (node (ref "R313") (pin "1") (pinfunction "1_1") (pintype "passive"))
      (node (ref "U28") (pin "2") (pinfunction "INT2_/_PWR_CTRL_2") (pintype "passive"))
    )
    (net (code "30") (name "/GYRO_RST") (class "Default")
      (node (ref "R318") (pin "2") (pinfunction "2_2") (pintype "passive"))
      (node (ref "R383") (pin "2") (pinfunction "2_2") (pintype "passive"))
      (node (ref "U28") (pin "4") (pinfunction "RST_B_4") (pintype "passive"))
    )
    (net (code "31") (name "/I2C1_SCL") (class "Default")
      (node (ref "U22") (pin "4") (pinfunction "SCL_/_SCLK_4") (pintype "passive"))
      (node (ref "U28") (pin "11") (pinfunction "SCL_/_SCLK_11") (pintype "passive"))
    )
    (net (code "32") (name "/I2C1_SDA") (class "Default")
      (node (ref "U22") (pin "6") (pinfunction "SDA_/_MOSI_6") (pintype "passive"))
      (node (ref "U28") (pin "12") (pinfunction "SDA_/_MOSI_/_SPI_Data_12") (pintype "passive"))
    )
    (net (code "33") (name "/I2C2_SCL") (class "Default")
      (node (ref "U24") (pin "1") (pinfunction "SCL_1") (pintype "passive"))
      (node (ref "U26") (pin "6") (pinfunction "SCL_6") (pintype "passive"))
    )
    (net (code "34") (name "/I2C2_SDA") (class "Default")
      (node (ref "U24") (pin "6") (pinfunction "SDA_6") (pintype "passive"))
      (node (ref "U26") (pin "1") (pinfunction "SDA_1") (pintype "passive"))
    )
    (net (code "35") (name "/IR_RCV") (class "Default")
      (node (ref "U23") (pin "1") (pinfunction "OUT_1") (pintype "passive"))
    )
    (net (code "36") (name "/RSTOUTn") (class "Default")
      (node (ref "R318") (pin "1") (pinfunction "1_1") (pintype "passive"))
      (node (ref "U29") (pin "2") (pinfunction "I_2") (pintype "passive"))
    )
    (net (code "37") (name "/SPLIT") (class "Default")
      (node (ref "C313") (pin "1") (pinfunction "1_1") (pintype "passive"))
      (node (ref "R246") (pin "1") (pinfunction "1_1") (pintype "passive"))
      (node (ref "R248") (pin "2") (pinfunction "2_2") (pintype "passive"))
      (node (ref "R249") (pin "2") (pinfunction "2_2") (pintype "passive"))
    )
    (net (code "38") (name "/SPLIT_R") (class "Default")
      (node (ref "R248") (pin "1") (pinfunction "1_1") (pintype "passive"))
      (node (ref "U19") (pin "5") (pinfunction "SPLIT_5") (pintype "passive"))
    )
    (net (code "39") (name "/TEMP_ADD0") (class "Default")
      (node (ref "R258") (pin "2") (pinfunction "2_2") (pintype "passive"))
      (node (ref "R259") (pin "2") (pinfunction "2_2") (pintype "passive"))
      (node (ref "U24") (pin "5") (pinfunction "ADD0_5") (pintype "passive"))
    )
    (net (code "40") (name "/TEMP_ALERT") (class "Default")
      (node (ref "U24") (pin "3") (pinfunction "ALERT_3") (pintype "passive"))
    )
    (net (code "41") (name "GND") (class "Default")
      (node (ref "C309") (pin "1") (pinfunction "1_1") (pintype "passive"))
      (node (ref "C310") (pin "2") (pinfunction "2_2") (pintype "passive"))
      (node (ref "C311") (pin "2") (pinfunction "2_2") (pintype "passive"))
      (node (ref "C312") (pin "2") (pinfunction "2_2") (pintype "passive"))
      (node (ref "C313") (pin "2") (pinfunction "2_2") (pintype "passive"))
      (node (ref "C325") (pin "2") (pinfunction "2_2") (pintype "passive"))
      (node (ref "C326") (pin "1") (pinfunction "1_1") (pintype "passive"))
      (node (ref "C329") (pin "2") (pinfunction "2_2") (pintype "passive"))
      (node (ref "C387") (pin "2") (pinfunction "2_2") (pintype "passive"))
      (node (ref "C388") (pin "2") (pinfunction "2_2") (pintype "passive"))
      (node (ref "C389") (pin "2") (pinfunction "2_2") (pintype "passive"))
      (node (ref "C391") (pin "2") (pinfunction "2_2") (pintype "passive"))
      (node (ref "C394") (pin "2") (pinfunction "2_2") (pintype "passive"))
      (node (ref "C396") (pin "2") (pinfunction "2_2") (pintype "passive"))
      (node (ref "C397") (pin "2") (pinfunction "2_2") (pintype "passive"))
      (node (ref "C398") (pin "2") (pinfunction "2_2") (pintype "passive"))
      (node (ref "C399") (pin "2") (pinfunction "2_2") (pintype "passive"))
      (node (ref "C400") (pin "2") (pinfunction "2_2") (pintype "passive"))
      (node (ref "C401") (pin "2") (pinfunction "2_2") (pintype "passive"))
      (node (ref "C402") (pin "2") (pinfunction "2_2") (pintype "passive"))
      (node (ref "C403") (pin "2") (pinfunction "2_2") (pintype "passive"))
      (node (ref "C405") (pin "2") (pinfunction "2_2") (pintype "passive"))
      (node (ref "C423") (pin "2") (pinfunction "2_2") (pintype "passive"))
      (node (ref "Q13") (pin "2") (pinfunction "SOURCE_2") (pintype "passive"))
      (node (ref "R250") (pin "1") (pinfunction "1_1") (pintype "passive"))
      (node (ref "R259") (pin "1") (pinfunction "1_1") (pintype "passive"))
      (node (ref "R310") (pin "1") (pinfunction "1_1") (pintype "passive"))
      (node (ref "R311") (pin "2") (pinfunction "2_2") (pintype "passive"))
      (node (ref "R316") (pin "2") (pinfunction "2_2") (pintype "passive"))
      (node (ref "U19") (pin "2") (pinfunction "GND_2") (pintype "passive"))
      (node (ref "U20") (pin "3") (pinfunction "GND_3") (pintype "power_in"))
      (node (ref "U22") (pin "12") (pinfunction "GND_2_12") (pintype "passive"))
      (node (ref "U22") (pin "13") (pinfunction "Reserved_2_13") (pintype "passive"))
      (node (ref "U22") (pin "5") (pinfunction "GND_1_5") (pintype "passive"))
      (node (ref "U22") (pin "7") (pinfunction "SA0_/_MISO_7") (pintype "passive"))
      (node (ref "U23") (pin "2") (pinfunction "GND_2") (pintype "passive"))
      (node (ref "U24") (pin "2") (pinfunction "GND_2") (pintype "passive"))
      (node (ref "U26") (pin "2") (pinfunction "VSS_2") (pintype "passive"))
      (node (ref "U26") (pin "7") (pinfunction "EPAD_7") (pintype "passive"))
      (node (ref "U28") (pin "1") (pinfunction "GND1_1") (pintype "passive"))
      (node (ref "U28") (pin "10") (pinfunction "RSVD_GND_4_10") (pintype "passive"))
      (node (ref "U28") (pin "13") (pinfunction "SA0_/_MISO_13") (pintype "passive"))
      (node (ref "U28") (pin "14") (pinfunction "GND3_14") (pintype "passive"))
      (node (ref "U28") (pin "19") (pinfunction "GND4_19") (pintype "passive"))
      (node (ref "U28") (pin "20") (pinfunction "RSVD_GND_5_20") (pintype "passive"))
      (node (ref "U28") (pin "21") (pinfunction "RSVD_GND_6_21") (pintype "passive"))
      (node (ref "U28") (pin "22") (pinfunction "RSVD_GND_7_22") (pintype "passive"))
      (node (ref "U28") (pin "23") (pinfunction "RSVD_GND_8_23") (pintype "passive"))
      (node (ref "U28") (pin "24") (pinfunction "RSVD_GND_9_24") (pintype "passive"))
      (node (ref "U28") (pin "5") (pinfunction "GND2_5") (pintype "passive"))
      (node (ref "U28") (pin "6") (pinfunction "RSVD_GND_1_6") (pintype "passive"))
      (node (ref "U28") (pin "7") (pinfunction "RSVD_GND_2_7") (pintype "passive"))
      (node (ref "U28") (pin "8") (pinfunction "I2C_B_/_SPI_8") (pintype "passive"))
      (node (ref "U28") (pin "9") (pinfunction "RSVD_GND_3_9") (pintype "passive"))
      (node (ref "U29") (pin "3") (pinfunction "GND_3") (pintype "passive"))
      (node (ref "U35") (pin "3") (pinfunction "GND_3") (pintype "power_in"))
    )
    (net (code "42") (name "Net-(U22-Reserved_1)") (class "Default")
      (node (ref "C390") (pin "2") (pinfunction "2_2") (pintype "passive"))
      (node (ref "R311") (pin "1") (pinfunction "1_1") (pintype "passive"))
      (node (ref "U22") (pin "3") (pinfunction "Reserved_1_3") (pintype "passive"))
    )
    (net (code "43") (name "unconnected-(U26-NC_1-Pad3)") (class "Default")
      (node (ref "U26") (pin "3") (pinfunction "NC_1_3") (pintype "passive+no_connect"))
    )
    (net (code "44") (name "unconnected-(U26-NC_2-Pad4)") (class "Default")
      (node (ref "U26") (pin "4") (pinfunction "NC_2_4") (pintype "passive+no_connect"))
    )
    (net (code "45") (name "unconnected-(U29-nc-Pad1)") (class "Default")
      (node (ref "U29") (pin "1") (pinfunction "nc_1") (pintype "passive+no_connect"))
    )
  )
)
